# Chargeur.net
KiCad netlist of a schematic drawn in Altium Designer
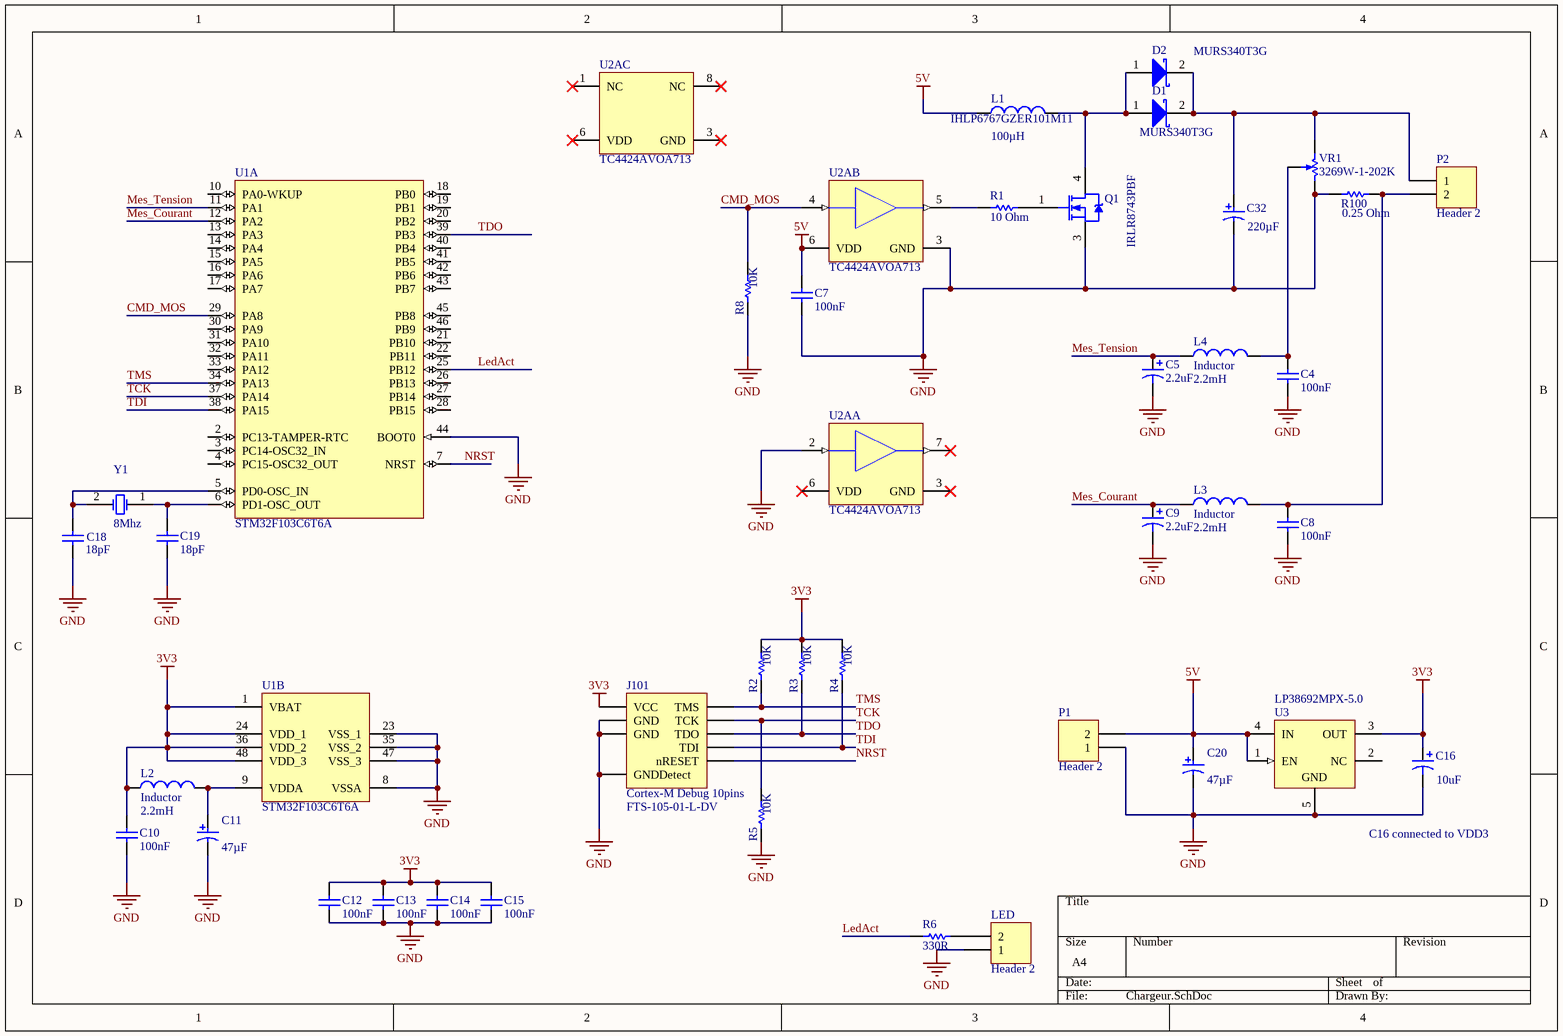
[diagram p0: Chargeur.SchDoc]

(export (version "E")
  (design (tool "Eeschema 10.0.6"))
  (components
    (comp (ref "C4")
      (value "100nF")
      (footprint "CAPC1206(3216)100_L")
      (description "CAP 100nF 25V ±10% 1206 (3216 Metric) Thickness 1mm SMD")
      (fields (field (name "TOLERANCE") "Â±10%") (field (name "Comment") "CAP 100nF 25V 1206(3216)"))
      (libsource (lib "Altium Content Vault") (part "CMP-1037-04193-1"))
    )
    (comp (ref "C5")
      (value "2.2uF")
      (footprint "B")
      (fields (field (name "Comment") "CC475B004M") (field (name "PUBLISHER") "Altium Limited"))
      (libsource (lib "Vishay Sprague Tantalum Chip Capacitor") (part "CC475B004M"))
    )
    (comp (ref "C7")
      (value "100nF")
      (footprint "CAPC1206(3216)100_L")
      (description "CAP 100nF 25V ±10% 1206 (3216 Metric) Thickness 1mm SMD")
      (fields (field (name "TOLERANCE") "Â±10%") (field (name "Comment") "CAP 100nF 25V 1206(3216)"))
      (libsource (lib "Altium Content Vault") (part "CMP-1037-04193-1"))
    )
    (comp (ref "C8")
      (value "100nF")
      (footprint "CAPC1206(3216)100_L")
      (description "CAP 100nF 25V ±10% 1206 (3216 Metric) Thickness 1mm SMD")
      (fields (field (name "TOLERANCE") "Â±10%") (field (name "Comment") "CAP 100nF 25V 1206(3216)"))
      (libsource (lib "Altium Content Vault") (part "CMP-1037-04193-1"))
    )
    (comp (ref "C9")
      (value "2.2uF")
      (footprint "B")
      (fields (field (name "Comment") "CC475B004M") (field (name "PUBLISHER") "Altium Limited"))
      (libsource (lib "Vishay Sprague Tantalum Chip Capacitor") (part "CC475B004M"))
    )
    (comp (ref "C10")
      (value "100nF")
      (footprint "CAPC1206(3216)100_L")
      (description "CAP 100nF 25V ±10% 1206 (3216 Metric) Thickness 1mm SMD")
      (fields (field (name "TOLERANCE") "Â±10%") (field (name "Comment") "CAP 100nF 25V 1206(3216)"))
      (libsource (lib "Altium Content Vault") (part "CMP-1037-04193-1"))
    )
    (comp (ref "C11")
      (value "47µF")
      (footprint "VISH-7343-31_M")
      (description "Tantalum Capacitor, 47 uF, +/- 10%, 16 V, -55 to 125 degC, 2917 (7343 Metric), RoHS, Tape and Reel")
      (fields (field (name "TOLERANCE") "1%") (field (name "Comment") "293D476X9016D2TE3"))
      (libsource (lib "Altium Content Vault") (part "CMP-1666-00025-1"))
    )
    (comp (ref "C12")
      (value "100nF")
      (footprint "CAPC1206(3216)100_L")
      (description "CAP 100nF 25V ±10% 1206 (3216 Metric) Thickness 1mm SMD")
      (fields (field (name "TOLERANCE") "Â±10%") (field (name "Comment") "CAP 100nF 25V 1206(3216)"))
      (libsource (lib "Altium Content Vault") (part "CMP-1037-04193-1"))
    )
    (comp (ref "C13")
      (value "100nF")
      (footprint "CAPC1206(3216)100_L")
      (description "CAP 100nF 25V ±10% 1206 (3216 Metric) Thickness 1mm SMD")
      (fields (field (name "TOLERANCE") "Â±10%") (field (name "Comment") "CAP 100nF 25V 1206(3216)"))
      (libsource (lib "Altium Content Vault") (part "CMP-1037-04193-1"))
    )
    (comp (ref "C14")
      (value "100nF")
      (footprint "CAPC1206(3216)100_L")
      (description "CAP 100nF 25V ±10% 1206 (3216 Metric) Thickness 1mm SMD")
      (fields (field (name "TOLERANCE") "Â±10%") (field (name "Comment") "CAP 100nF 25V 1206(3216)"))
      (libsource (lib "Altium Content Vault") (part "CMP-1037-04193-1"))
    )
    (comp (ref "C15")
      (value "100nF")
      (footprint "CAPC1206(3216)100_L")
      (description "CAP 100nF 25V ±10% 1206 (3216 Metric) Thickness 1mm SMD")
      (fields (field (name "TOLERANCE") "Â±10%") (field (name "Comment") "CAP 100nF 25V 1206(3216)"))
      (libsource (lib "Altium Content Vault") (part "CMP-1037-04193-1"))
    )
    (comp (ref "C16")
      (value "10uF")
      (footprint "C")
      (fields (field (name "Comment") "194D335X0015C2") (field (name "PUBLISHER") "Altium Limited"))
      (libsource (lib "Vishay Sprague Tantalum Chip Capacitor") (part "194D335X0015C2"))
    )
    (comp (ref "C18")
      (value "18pF")
      (footprint "CAPC1206(3216)100_L")
      (description "CAP 100nF 25V ±10% 1206 (3216 Metric) Thickness 1mm SMD")
      (fields (field (name "TOLERANCE") "Â±10%") (field (name "Comment") "CAP 100nF 25V 1206(3216)"))
      (libsource (lib "Altium Content Vault") (part "CMP-1037-04193-1"))
    )
    (comp (ref "C19")
      (value "18pF")
      (footprint "CAPC1206(3216)100_L")
      (description "CAP 100nF 25V ±10% 1206 (3216 Metric) Thickness 1mm SMD")
      (fields (field (name "TOLERANCE") "Â±10%") (field (name "Comment") "CAP 100nF 25V 1206(3216)"))
      (libsource (lib "Altium Content Vault") (part "CMP-1037-04193-1"))
    )
    (comp (ref "C20")
      (value "47µF")
      (footprint "VISH-7343-31_M")
      (description "Tantalum Capacitor, 47 uF, +/- 10%, 16 V, -55 to 125 degC, 2917 (7343 Metric), RoHS, Tape and Reel")
      (fields (field (name "TOLERANCE") "1%") (field (name "Comment") "293D476X9016D2TE3"))
      (libsource (lib "Altium Content Vault") (part "CMP-1666-00025-1"))
    )
    (comp (ref "C32")
      (value "220µF")
      (footprint "VISH-7343-31_M")
      (description "Tantalum Capacitor, 47 uF, +/- 10%, 16 V, -55 to 125 degC, 2917 (7343 Metric), RoHS, Tape and Reel")
      (fields (field (name "TOLERANCE") "1%") (field (name "Comment") "293D476X9016D2TE3"))
      (libsource (lib "Altium Content Vault") (part "CMP-1666-00025-1"))
    )
    (comp (ref "D1")
      (value "MURS340T3G")
      (footprint "VISH-DO-214AB-2_V")
      (libsource (lib "Altium Content Vault") (part "CMP-1666-00013-4"))
    )
    (comp (ref "D2")
      (value "MURS340T3G")
      (footprint "VISH-DO-214AB-2_V")
      (libsource (lib "Altium Content Vault") (part "CMP-1666-00013-4"))
    )
    (comp (ref "J101")
      (value "Cortex-M Debug 10pins")
      (footprint "2199SB-10G-301523")
      (fields (field (name "COMMENT2") "FTS-105-01-L-DV"))
      (libsource (lib "INSA") (part "Cortex-M Debug 10pins"))
    )
    (comp (ref "L1")
      (value "IHLP6767GZER101M11")
      (footprint "IHLP-6767GZ-11")
      (description "Inductor")
      (fields (field (name "ALTIUM_VALUE") "100µH") (field (name "PUBLISHER") "Altium Limited"))
      (libsource (lib "Miscellaneous Devices") (part "Inductor"))
    )
    (comp (ref "L2")
      (value "Inductor")
      (footprint "INDC3216AL")
      (fields (field (name "ALTIUM_VALUE") "2.2mH") (field (name "PUBLISHER") "Altium Limited"))
      (libsource (lib "Miscellaneous Devices") (part "Inductor"))
    )
    (comp (ref "L3")
      (value "Inductor")
      (footprint "INDC3216AL")
      (fields (field (name "ALTIUM_VALUE") "2.2mH") (field (name "PUBLISHER") "Altium Limited"))
      (libsource (lib "Miscellaneous Devices") (part "Inductor"))
    )
    (comp (ref "L4")
      (value "Inductor")
      (footprint "INDC3216AL")
      (fields (field (name "ALTIUM_VALUE") "2.2mH") (field (name "PUBLISHER") "Altium Limited"))
      (libsource (lib "Miscellaneous Devices") (part "Inductor"))
    )
    (comp (ref "LED")
      (value "Header 2")
      (footprint "HDR1X2")
      (description "Header, 2-Pin")
      (fields (field (name "PUBLISHER") "Altium Limited"))
      (libsource (lib "") (part "Header 2_2"))
    )
    (comp (ref "P1")
      (value "Header 2")
      (footprint "HDR1X2")
      (description "Header, 2-Pin")
      (fields (field (name "PUBLISHER") "Altium Limited"))
      (libsource (lib "") (part "Header 2_1"))
    )
    (comp (ref "P2")
      (value "Header 2")
      (footprint "HDR1X2")
      (description "Header, 2-Pin")
      (fields (field (name "PUBLISHER") "Altium Limited"))
      (libsource (lib "Miscellaneous Connectors") (part "Header 2"))
    )
    (comp (ref "Q1")
      (value "IRLR8743PBF")
      (footprint "TO-252AA_N")
      (description "HEXFET Power MOSFET")
      (fields (field (name "PUBLISHER") "Altium Limited"))
      (libsource (lib "IR Discrete MOSFET - Power") (part "IRFR13N20D"))
    )
    (comp (ref "R1")
      (value "10 Ohm")
      (footprint "RESC1206(3216)_N")
      (description "470R 0.25W 5% 1206 (3216 Metric)  SMD")
      (fields (field (name "TOLERANCE") "5 %") (field (name "POWER") "0.25 W"))
      (libsource (lib "Altium Content Vault") (part "CMP-1014-00066-1"))
    )
    (comp (ref "R2")
      (value "10K")
      (footprint "RESC1206(3216)_M")
      (description "10K 0.25W 5% 1206 (3216 Metric)  SMD")
      (fields (field (name "POWER") "0.25 W") (field (name "TOLERANCE") "5 %"))
      (libsource (lib "Altium Content Vault") (part "CMP-1014-00098-1"))
    )
    (comp (ref "R3")
      (value "10K")
      (footprint "RESC1206(3216)_M")
      (description "10K 0.25W 5% 1206 (3216 Metric)  SMD")
      (fields (field (name "POWER") "0.25 W") (field (name "TOLERANCE") "5 %"))
      (libsource (lib "Altium Content Vault") (part "CMP-1014-00098-1"))
    )
    (comp (ref "R4")
      (value "10K")
      (footprint "RESC1206(3216)_M")
      (description "10K 0.25W 5% 1206 (3216 Metric)  SMD")
      (fields (field (name "POWER") "0.25 W") (field (name "TOLERANCE") "5 %"))
      (libsource (lib "Altium Content Vault") (part "CMP-1014-00098-1"))
    )
    (comp (ref "R5")
      (value "10K")
      (footprint "RESC1206(3216)_M")
      (description "10K 0.25W 5% 1206 (3216 Metric)  SMD")
      (fields (field (name "POWER") "0.25 W") (field (name "TOLERANCE") "5 %"))
      (libsource (lib "Altium Content Vault") (part "CMP-1014-00098-1"))
    )
    (comp (ref "R6")
      (value "330R")
      (footprint "RESC1206(3216)_M")
      (description "10K 0.25W 5% 1206 (3216 Metric)  SMD")
      (fields (field (name "POWER") "0.25 W") (field (name "TOLERANCE") "5 %"))
      (libsource (lib "Altium Content Vault") (part "CMP-1014-00098-1"))
    )
    (comp (ref "R8")
      (value "10K")
      (footprint "RESC1206(3216)_M")
      (description "10K 0.25W 5% 1206 (3216 Metric)  SMD")
      (fields (field (name "POWER") "0.25 W") (field (name "TOLERANCE") "5 %"))
      (libsource (lib "Altium Content Vault") (part "CMP-1014-00098-1"))
    )
    (comp (ref "R100")
      (value "0.25 Ohm")
      (footprint "RESC2010(5025)_L")
      (description "1R 0.75W 5% 2010 (5025 Metric)  SMD")
      (fields (field (name "TOLERANCE") "5 %") (field (name "POWER") "0.75 W"))
      (libsource (lib "Altium Content Vault") (part "CMP-1017-00002-1"))
    )
    (comp (ref "U1")
      (value "STM32F103C6T6A")
      (footprint "STM-LQFP48_M")
      (libsource (lib "Altium Content Vault") (part "MC-ARM-STM32F103X4_6-SQ48"))
    )
    (comp (ref "U2A")
      (value "TC4424AVOA713")
      (footprint "SOIC-OA8_N")
      (description "3A Dual High-Speed Power MOSFET Drivers, Non Inverting, Extended Temperature, Tape and Reel")
      (fields (field (name "PUBLISHER") "Altium Limited"))
      (libsource (lib "Microchip Power Mgt MOSFET Driver") (part "TC4424AVOA713"))
    )
    (comp (ref "U3")
      (value "LP38692MPX-5.0")
      (footprint "MP05A_M")
      (description "1A Low Dropout CMOS Linear Regulators, Stable with Ceramic Output Capacitors, 5-pin SOT-223")
      (fields (field (name "MANUFACTURER") "National Semiconductor"))
      (libsource (lib "Altium Content Vault") (part "CMP-0062-01830-1"))
    )
    (comp (ref "VR1")
      (value "3269W-1-202K")
      (footprint "3269W")
      (description "Square Trimming Potentiometer")
      (fields (field (name "PUBLISHER") "Altium Limited"))
      (libsource (lib "Miscellaneous Devices") (part "RPot SM"))
    )
    (comp (ref "Y1")
      (value "8Mhz")
      (footprint "HC49/4H_SMX")
      (description "Surface Mount Quartz Crystal")
      (fields (field (name "Comment") "HC49/4H_SMX") (field (name "PUBLISHER") "Altium Limited"))
      (libsource (lib "C-MAC Crystal Oscillator") (part "HC49/4H_SMX"))
    )
  )
  (nets
    (net (code "1") (name "/CMD_MOS") (class "Default")
      (node (ref "R8") (pin "2") (pinfunction "2_2") (pintype "passive"))
      (node (ref "U1") (pin "29") (pinfunction "PA8_29") (pintype "bidirectional"))
      (node (ref "U2A") (pin "4") (pinfunction "INB_4") (pintype "input"))
    )
    (net (code "2") (name "/LedAct") (class "Default")
      (node (ref "R6") (pin "2") (pinfunction "2_2") (pintype "passive"))
      (node (ref "U1") (pin "25") (pinfunction "PB12_25") (pintype "bidirectional"))
    )
    (net (code "3") (name "/Mes_Courant") (class "Default")
      (node (ref "C9") (pin "1") (pinfunction "1_1") (pintype "passive"))
      (node (ref "L3") (pin "1") (pinfunction "1_1") (pintype "passive"))
      (node (ref "U1") (pin "12") (pinfunction "PA2_12") (pintype "bidirectional"))
    )
    (net (code "4") (name "/Mes_Tension") (class "Default")
      (node (ref "C5") (pin "1") (pinfunction "1_1") (pintype "passive"))
      (node (ref "L4") (pin "1") (pinfunction "1_1") (pintype "passive"))
      (node (ref "U1") (pin "11") (pinfunction "PA1_11") (pintype "bidirectional"))
    )
    (net (code "5") (name "/NRST") (class "Default")
      (node (ref "J101") (pin "10") (pinfunction "nRESET_10") (pintype "passive"))
      (node (ref "U1") (pin "7") (pinfunction "NRST_7") (pintype "bidirectional"))
    )
    (net (code "6") (name "/TCK") (class "Default")
      (node (ref "J101") (pin "4") (pinfunction "TCK_4") (pintype "passive"))
      (node (ref "R5") (pin "2") (pinfunction "2_2") (pintype "passive"))
      (node (ref "U1") (pin "37") (pinfunction "PA14_37") (pintype "bidirectional"))
    )
    (net (code "7") (name "/TDI") (class "Default")
      (node (ref "J101") (pin "8") (pinfunction "TDI_8") (pintype "passive"))
      (node (ref "R4") (pin "1") (pinfunction "1_1") (pintype "passive"))
      (node (ref "U1") (pin "38") (pinfunction "PA15_38") (pintype "bidirectional"))
    )
    (net (code "8") (name "/TDO") (class "Default")
      (node (ref "J101") (pin "6") (pinfunction "TDO_6") (pintype "passive"))
      (node (ref "R3") (pin "1") (pinfunction "1_1") (pintype "passive"))
      (node (ref "U1") (pin "39") (pinfunction "PB3_39") (pintype "bidirectional"))
    )
    (net (code "9") (name "/TMS") (class "Default")
      (node (ref "J101") (pin "2") (pinfunction "TMS_2") (pintype "passive"))
      (node (ref "R2") (pin "1") (pinfunction "1_1") (pintype "passive"))
      (node (ref "U1") (pin "34") (pinfunction "PA13_34") (pintype "bidirectional"))
    )
    (net (code "10") (name "3V3") (class "Default")
      (node (ref "C10") (pin "2") (pinfunction "2_2") (pintype "passive"))
      (node (ref "C12") (pin "2") (pinfunction "2_2") (pintype "passive"))
      (node (ref "C13") (pin "2") (pinfunction "2_2") (pintype "passive"))
      (node (ref "C14") (pin "2") (pinfunction "2_2") (pintype "passive"))
      (node (ref "C15") (pin "2") (pinfunction "2_2") (pintype "passive"))
      (node (ref "C16") (pin "1") (pinfunction "1_1") (pintype "passive"))
      (node (ref "J101") (pin "1") (pinfunction "VCC_1") (pintype "passive"))
      (node (ref "L2") (pin "1") (pinfunction "1_1") (pintype "passive"))
      (node (ref "R2") (pin "2") (pinfunction "2_2") (pintype "passive"))
      (node (ref "R3") (pin "2") (pinfunction "2_2") (pintype "passive"))
      (node (ref "R4") (pin "2") (pinfunction "2_2") (pintype "passive"))
      (node (ref "U1") (pin "1") (pinfunction "VBAT_1") (pintype "power_in"))
      (node (ref "U1") (pin "24") (pinfunction "VDD_1_24") (pintype "power_in"))
      (node (ref "U1") (pin "36") (pinfunction "VDD_2_36") (pintype "power_in"))
      (node (ref "U1") (pin "48") (pinfunction "VDD_3_48") (pintype "power_in"))
      (node (ref "U3") (pin "3") (pinfunction "OUT_3") (pintype "power_in"))
    )
    (net (code "11") (name "5V") (class "Default")
      (node (ref "C20") (pin "1") (pinfunction "1_1") (pintype "passive"))
      (node (ref "C7") (pin "2") (pinfunction "2_2") (pintype "passive"))
      (node (ref "L1") (pin "1") (pinfunction "1_1") (pintype "passive"))
      (node (ref "P1") (pin "2") (pinfunction "2_2") (pintype "passive"))
      (node (ref "U2A") (pin "6") (pinfunction "VDD_6") (pintype "power_in"))
      (node (ref "U3") (pin "1") (pinfunction "EN_1") (pintype "input"))
      (node (ref "U3") (pin "4") (pinfunction "IN_4") (pintype "power_in"))
    )
    (net (code "12") (name "GND") (class "Default")
      (node (ref "C10") (pin "1") (pinfunction "1_1") (pintype "passive"))
      (node (ref "C11") (pin "2") (pinfunction "2_2") (pintype "passive"))
      (node (ref "C12") (pin "1") (pinfunction "1_1") (pintype "passive"))
      (node (ref "C13") (pin "1") (pinfunction "1_1") (pintype "passive"))
      (node (ref "C14") (pin "1") (pinfunction "1_1") (pintype "passive"))
      (node (ref "C15") (pin "1") (pinfunction "1_1") (pintype "passive"))
      (node (ref "C16") (pin "2") (pinfunction "2_2") (pintype "passive"))
      (node (ref "C18") (pin "1") (pinfunction "1_1") (pintype "passive"))
      (node (ref "C19") (pin "1") (pinfunction "1_1") (pintype "passive"))
      (node (ref "C20") (pin "2") (pinfunction "2_2") (pintype "passive"))
      (node (ref "C32") (pin "2") (pinfunction "2_2") (pintype "passive"))
      (node (ref "C4") (pin "1") (pinfunction "1_1") (pintype "passive"))
      (node (ref "C5") (pin "2") (pinfunction "2_2") (pintype "passive"))
      (node (ref "C7") (pin "1") (pinfunction "1_1") (pintype "passive"))
      (node (ref "C8") (pin "1") (pinfunction "1_1") (pintype "passive"))
      (node (ref "C9") (pin "2") (pinfunction "2_2") (pintype "passive"))
      (node (ref "J101") (pin "3") (pinfunction "GND_3") (pintype "passive"))
      (node (ref "J101") (pin "5") (pinfunction "GND_5") (pintype "passive"))
      (node (ref "J101") (pin "9") (pinfunction "GNDDetect_9") (pintype "passive"))
      (node (ref "LED") (pin "1") (pinfunction "1_1") (pintype "passive"))
      (node (ref "P1") (pin "1") (pinfunction "1_1") (pintype "passive"))
      (node (ref "Q1") (pin "3") (pinfunction "S_3") (pintype "passive"))
      (node (ref "R100") (pin "1") (pinfunction "1_1") (pintype "passive"))
      (node (ref "R5") (pin "1") (pinfunction "1_1") (pintype "passive"))
      (node (ref "R8") (pin "1") (pinfunction "1_1") (pintype "passive"))
      (node (ref "U1") (pin "23") (pinfunction "VSS_1_23") (pintype "power_in"))
      (node (ref "U1") (pin "35") (pinfunction "VSS_2_35") (pintype "power_in"))
      (node (ref "U1") (pin "44") (pinfunction "BOOT0_44") (pintype "input"))
      (node (ref "U1") (pin "47") (pinfunction "VSS_3_47") (pintype "power_in"))
      (node (ref "U1") (pin "8") (pinfunction "VSSA_8") (pintype "power_in"))
      (node (ref "U2A") (pin "2") (pinfunction "INA_2") (pintype "input"))
      (node (ref "U2A") (pin "3") (pinfunction "GND_3") (pintype "power_in"))
      (node (ref "U3") (pin "5") (pinfunction "GND_5") (pintype "power_in"))
      (node (ref "VR1") (pin "CCW") (pinfunction "-_CCW") (pintype "passive"))
    )
    (net (code "13") (name "Net-(C4-Pad2)") (class "Default")
      (node (ref "C4") (pin "2") (pinfunction "2_2") (pintype "passive"))
      (node (ref "L4") (pin "2") (pinfunction "2_2") (pintype "passive"))
      (node (ref "VR1") (pin "W") (pinfunction "W_W") (pintype "passive"))
    )
    (net (code "14") (name "Net-(C8-Pad2)") (class "Default")
      (node (ref "C8") (pin "2") (pinfunction "2_2") (pintype "passive"))
      (node (ref "L3") (pin "2") (pinfunction "2_2") (pintype "passive"))
      (node (ref "P2") (pin "2") (pinfunction "2_2") (pintype "passive"))
      (node (ref "R100") (pin "2") (pinfunction "2_2") (pintype "passive"))
    )
    (net (code "15") (name "Net-(D1-A)") (class "Default")
      (node (ref "D1") (pin "1") (pinfunction "A_1") (pintype "passive"))
      (node (ref "D2") (pin "1") (pinfunction "A_1") (pintype "passive"))
      (node (ref "L1") (pin "2") (pinfunction "2_2") (pintype "passive"))
      (node (ref "Q1") (pin "4") (pinfunction "D_4") (pintype "passive"))
    )
    (net (code "16") (name "Net-(D1-K)") (class "Default")
      (node (ref "C32") (pin "1") (pinfunction "1_1") (pintype "passive"))
      (node (ref "D1") (pin "2") (pinfunction "K_2") (pintype "passive"))
      (node (ref "D2") (pin "2") (pinfunction "K_2") (pintype "passive"))
      (node (ref "P2") (pin "1") (pinfunction "1_1") (pintype "passive"))
      (node (ref "VR1") (pin "CW") (pinfunction "+_CW") (pintype "passive"))
    )
    (net (code "17") (name "Net-(LED-Pad2)") (class "Default")
      (node (ref "LED") (pin "2") (pinfunction "2_2") (pintype "passive"))
      (node (ref "R6") (pin "1") (pinfunction "1_1") (pintype "passive"))
    )
    (net (code "18") (name "Net-(Q1-G)") (class "Default")
      (node (ref "Q1") (pin "1") (pinfunction "G_1") (pintype "passive"))
      (node (ref "R1") (pin "1") (pinfunction "1_1") (pintype "passive"))
    )
    (net (code "19") (name "Net-(U1A-PD0-OSC_IN)") (class "Default")
      (node (ref "C18") (pin "2") (pinfunction "2_2") (pintype "passive"))
      (node (ref "U1") (pin "5") (pinfunction "PD0-OSC_IN_5") (pintype "bidirectional"))
      (node (ref "Y1") (pin "2") (pinfunction "OSC2_2") (pintype "passive"))
    )
    (net (code "20") (name "Net-(U1A-PD1-OSC_OUT)") (class "Default")
      (node (ref "C19") (pin "2") (pinfunction "2_2") (pintype "passive"))
      (node (ref "U1") (pin "6") (pinfunction "PD1-OSC_OUT_6") (pintype "bidirectional"))
      (node (ref "Y1") (pin "1") (pinfunction "OSC1_1") (pintype "passive"))
    )
    (net (code "21") (name "Net-(U1B-VDDA)") (class "Default")
      (node (ref "C11") (pin "1") (pinfunction "1_1") (pintype "passive"))
      (node (ref "L2") (pin "2") (pinfunction "2_2") (pintype "passive"))
      (node (ref "U1") (pin "9") (pinfunction "VDDA_9") (pintype "power_in"))
    )
    (net (code "22") (name "Net-(U2AB-OUTB)") (class "Default")
      (node (ref "R1") (pin "2") (pinfunction "2_2") (pintype "passive"))
      (node (ref "U2A") (pin "5") (pinfunction "OUTB_5") (pintype "output"))
    )
    (net (code "23") (name "unconnected-(U1A-PA0-WKUP-Pad10)") (class "Default")
      (node (ref "U1") (pin "10") (pinfunction "PA0-WKUP_10") (pintype "bidirectional"))
    )
    (net (code "24") (name "unconnected-(U1A-PA3-Pad13)") (class "Default")
      (node (ref "U1") (pin "13") (pinfunction "PA3_13") (pintype "bidirectional"))
    )
    (net (code "25") (name "unconnected-(U1A-PA4-Pad14)") (class "Default")
      (node (ref "U1") (pin "14") (pinfunction "PA4_14") (pintype "bidirectional"))
    )
    (net (code "26") (name "unconnected-(U1A-PA5-Pad15)") (class "Default")
      (node (ref "U1") (pin "15") (pinfunction "PA5_15") (pintype "bidirectional"))
    )
    (net (code "27") (name "unconnected-(U1A-PA6-Pad16)") (class "Default")
      (node (ref "U1") (pin "16") (pinfunction "PA6_16") (pintype "bidirectional"))
    )
    (net (code "28") (name "unconnected-(U1A-PA7-Pad17)") (class "Default")
      (node (ref "U1") (pin "17") (pinfunction "PA7_17") (pintype "bidirectional"))
    )
    (net (code "29") (name "unconnected-(U1A-PA9-Pad30)") (class "Default")
      (node (ref "U1") (pin "30") (pinfunction "PA9_30") (pintype "bidirectional"))
    )
    (net (code "30") (name "unconnected-(U1A-PA10-Pad31)") (class "Default")
      (node (ref "U1") (pin "31") (pinfunction "PA10_31") (pintype "bidirectional"))
    )
    (net (code "31") (name "unconnected-(U1A-PA11-Pad32)") (class "Default")
      (node (ref "U1") (pin "32") (pinfunction "PA11_32") (pintype "bidirectional"))
    )
    (net (code "32") (name "unconnected-(U1A-PA12-Pad33)") (class "Default")
      (node (ref "U1") (pin "33") (pinfunction "PA12_33") (pintype "bidirectional"))
    )
    (net (code "33") (name "unconnected-(U1A-PB0-Pad18)") (class "Default")
      (node (ref "U1") (pin "18") (pinfunction "PB0_18") (pintype "bidirectional"))
    )
    (net (code "34") (name "unconnected-(U1A-PB1-Pad19)") (class "Default")
      (node (ref "U1") (pin "19") (pinfunction "PB1_19") (pintype "bidirectional"))
    )
    (net (code "35") (name "unconnected-(U1A-PB2-Pad20)") (class "Default")
      (node (ref "U1") (pin "20") (pinfunction "PB2_20") (pintype "bidirectional"))
    )
    (net (code "36") (name "unconnected-(U1A-PB4-Pad40)") (class "Default")
      (node (ref "U1") (pin "40") (pinfunction "PB4_40") (pintype "bidirectional"))
    )
    (net (code "37") (name "unconnected-(U1A-PB5-Pad41)") (class "Default")
      (node (ref "U1") (pin "41") (pinfunction "PB5_41") (pintype "bidirectional"))
    )
    (net (code "38") (name "unconnected-(U1A-PB6-Pad42)") (class "Default")
      (node (ref "U1") (pin "42") (pinfunction "PB6_42") (pintype "bidirectional"))
    )
    (net (code "39") (name "unconnected-(U1A-PB7-Pad43)") (class "Default")
      (node (ref "U1") (pin "43") (pinfunction "PB7_43") (pintype "bidirectional"))
    )
    (net (code "40") (name "unconnected-(U1A-PB8-Pad45)") (class "Default")
      (node (ref "U1") (pin "45") (pinfunction "PB8_45") (pintype "bidirectional"))
    )
    (net (code "41") (name "unconnected-(U1A-PB9-Pad46)") (class "Default")
      (node (ref "U1") (pin "46") (pinfunction "PB9_46") (pintype "bidirectional"))
    )
    (net (code "42") (name "unconnected-(U1A-PB10-Pad21)") (class "Default")
      (node (ref "U1") (pin "21") (pinfunction "PB10_21") (pintype "bidirectional"))
    )
    (net (code "43") (name "unconnected-(U1A-PB11-Pad22)") (class "Default")
      (node (ref "U1") (pin "22") (pinfunction "PB11_22") (pintype "bidirectional"))
    )
    (net (code "44") (name "unconnected-(U1A-PB13-Pad26)") (class "Default")
      (node (ref "U1") (pin "26") (pinfunction "PB13_26") (pintype "bidirectional"))
    )
    (net (code "45") (name "unconnected-(U1A-PB14-Pad27)") (class "Default")
      (node (ref "U1") (pin "27") (pinfunction "PB14_27") (pintype "bidirectional"))
    )
    (net (code "46") (name "unconnected-(U1A-PB15-Pad28)") (class "Default")
      (node (ref "U1") (pin "28") (pinfunction "PB15_28") (pintype "bidirectional"))
    )
    (net (code "47") (name "unconnected-(U1A-PC13-TAMPER-RTC-Pad2)") (class "Default")
      (node (ref "U1") (pin "2") (pinfunction "PC13-TAMPER-RTC_2") (pintype "bidirectional"))
    )
    (net (code "48") (name "unconnected-(U1A-PC14-OSC32_IN-Pad3)") (class "Default")
      (node (ref "U1") (pin "3") (pinfunction "PC14-OSC32_IN_3") (pintype "bidirectional"))
    )
    (net (code "49") (name "unconnected-(U1A-PC15-OSC32_OUT-Pad4)") (class "Default")
      (node (ref "U1") (pin "4") (pinfunction "PC15-OSC32_OUT_4") (pintype "bidirectional"))
    )
    (net (code "50") (name "unconnected-(U2AA-GND-Pad3)") (class "Default")
      (node (ref "U2A") (pin "3") (pinfunction "GND_3") (pintype "power_in+no_connect"))
    )
    (net (code "51") (name "unconnected-(U2AA-OUTA-Pad7)") (class "Default")
      (node (ref "U2A") (pin "7") (pinfunction "OUTA_7") (pintype "output+no_connect"))
    )
    (net (code "52") (name "unconnected-(U2AA-VDD-Pad6)") (class "Default")
      (node (ref "U2A") (pin "6") (pinfunction "VDD_6") (pintype "power_in+no_connect"))
    )
    (net (code "53") (name "unconnected-(U2AC-GND-Pad3)") (class "Default")
      (node (ref "U2A") (pin "3") (pinfunction "GND_3") (pintype "power_in+no_connect"))
    )
    (net (code "54") (name "unconnected-(U2AC-NC-Pad1)") (class "Default")
      (node (ref "U2A") (pin "1") (pinfunction "NC_1") (pintype "passive+no_connect"))
    )
    (net (code "55") (name "unconnected-(U2AC-NC-Pad8)") (class "Default")
      (node (ref "U2A") (pin "8") (pinfunction "NC_8") (pintype "passive+no_connect"))
    )
    (net (code "56") (name "unconnected-(U2AC-VDD-Pad6)") (class "Default")
      (node (ref "U2A") (pin "6") (pinfunction "VDD_6") (pintype "power_in+no_connect"))
    )
    (net (code "57") (name "unconnected-(U3-NC-Pad2)") (class "Default")
      (node (ref "U3") (pin "2") (pinfunction "NC_2") (pintype "passive"))
    )
  )
)
